# 51.net
KiCad netlist of a schematic drawn in Altium Designer
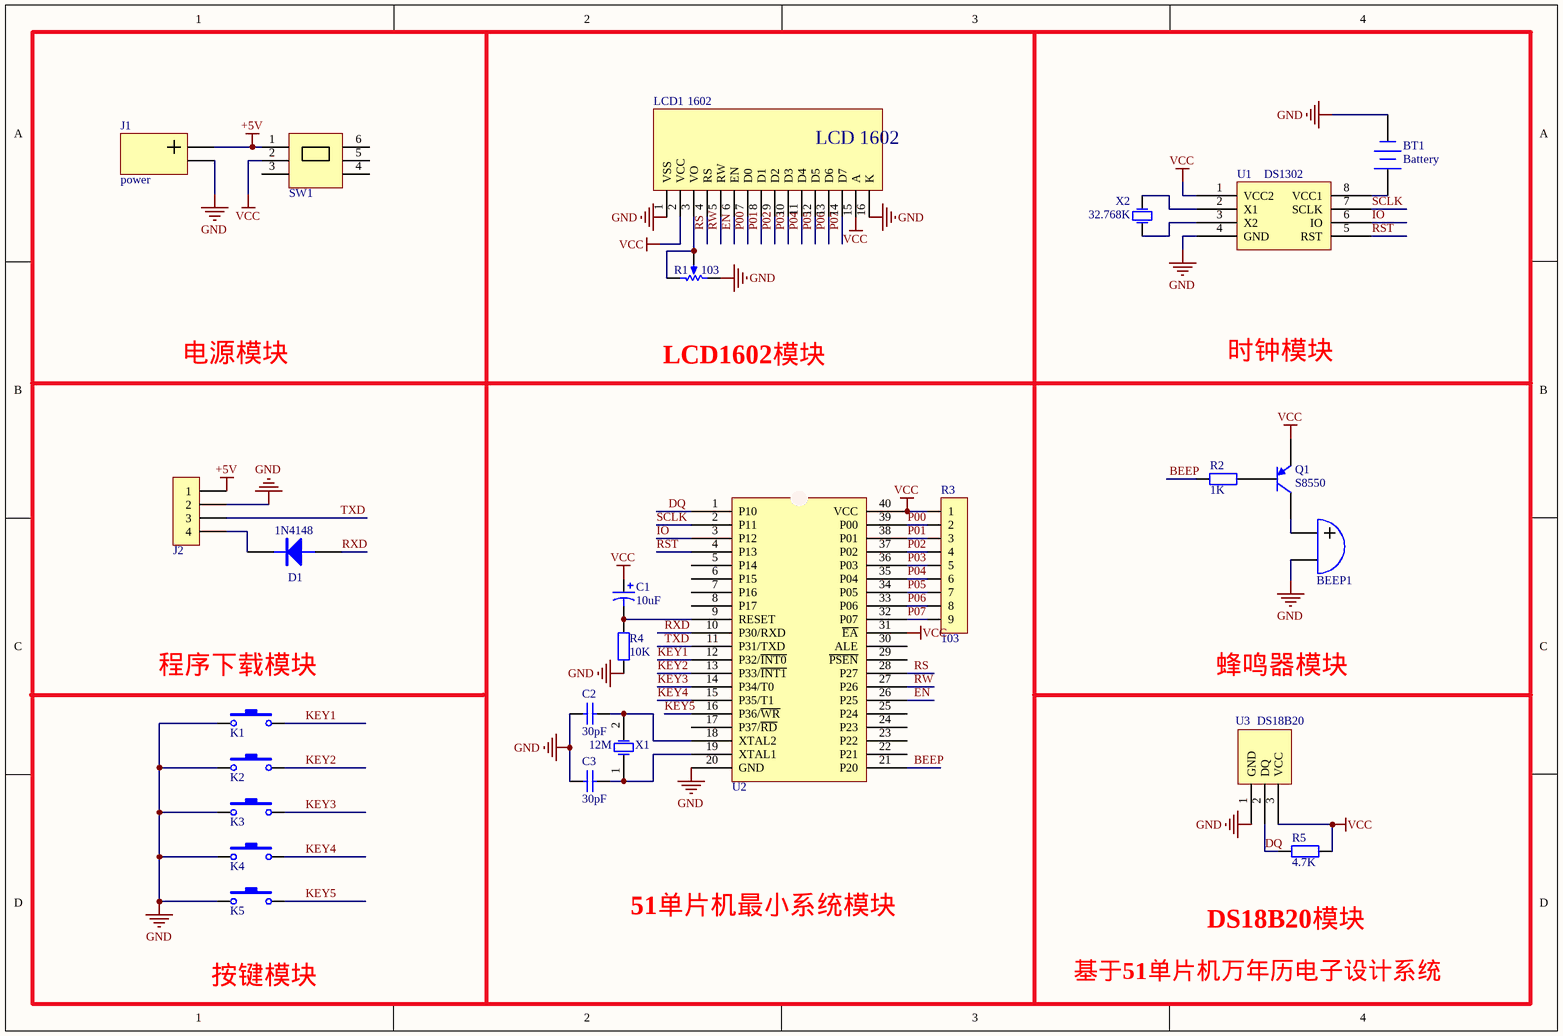
[diagram p0: 基于51单片机万年历电子设计系统.SchDoc]

(export (version "E")
  (design (tool "Eeschema 10.0.6"))
  (components
    (comp (ref "BEEP1") (value "BEEP") (footprint "BEEP") (libsource (lib "原理图库") (part "BEEP")))
    (comp (ref "BT1") (value "Battery") (footprint "CR-2032") (libsource (lib "MANUAL") (part "Battery")))
    (comp (ref "C1") (value "10uF") (footprint "CAP_2") (libsource (lib "原理图库") (part "CAP_2")))
    (comp (ref "C2") (value "30pF") (footprint "CAP") (libsource (lib "原理图库") (part "CAP")))
    (comp (ref "C3") (value "30pF") (footprint "CAP") (libsource (lib "原理图库") (part "CAP")))
    (comp (ref "D1") (value "1N4148") (footprint "1N4148") (libsource (lib "原理图库") (part "1N4148")))
    (comp (ref "J1") (value "power") (footprint "DC3.5") (libsource (lib "原理图库") (part "DC5.5")))
    (comp (ref "J2") (value "SENSOR") (footprint "SIP4") (libsource (lib "基于单片机温湿度报警器（带风扇）") (part "CON4")))
    (comp (ref "K1") (value "KEY") (footprint "SW2") (libsource (lib "原理图库") (part "KEY")))
    (comp (ref "K2") (value "KEY") (footprint "SW2") (libsource (lib "原理图库") (part "KEY")))
    (comp (ref "K3") (value "KEY") (footprint "SW2") (libsource (lib "原理图库") (part "KEY")))
    (comp (ref "K4") (value "KEY") (footprint "SW2") (libsource (lib "原理图库") (part "KEY")))
    (comp (ref "K5") (value "KEY") (footprint "SW2") (libsource (lib "原理图库") (part "KEY")))
    (comp (ref "LCD1") (value "1602") (footprint "1602") (libsource (lib "原理图库") (part "1602")))
    (comp (ref "Q1") (value "S8550") (footprint "PNP") (libsource (lib "原理图库") (part "PNP")))
    (comp (ref "R1") (value "103") (footprint "RES-B") (libsource (lib "原理图库") (part "RES-B")))
    (comp (ref "R2") (value "1K") (footprint "RES") (libsource (lib "") (part "Res_1")))
    (comp (ref "R3") (value "103") (footprint "SIP9") (libsource (lib "原理图库") (part "Header9")))
    (comp (ref "R4") (value "10K") (footprint "RES") (libsource (lib "原理图库") (part "Res")))
    (comp (ref "R5") (value "4.7K") (footprint "RES") (libsource (lib "") (part "Res_1")))
    (comp (ref "SW1") (value "SWT") (footprint "SWT") (libsource (lib "原理图库") (part "SWT")))
    (comp (ref "U1") (value "DS1302") (footprint "DIP8") (libsource (lib "MANUAL") (part "DS1302")))
    (comp (ref "U2") (value "STC89C52") (footprint "DIP40") (libsource (lib "原理图库") (part "STC89C52")))
    (comp (ref "U3") (value "DS18B20") (footprint "DS18B20") (libsource (lib "原理图库") (part "DS18B20")))
    (comp (ref "X1") (value "12M") (footprint "JZ") (libsource (lib "原理图库") (part "XTAL")))
    (comp (ref "X2") (value "32.768K") (footprint "XTAL2") (libsource (lib "Factory") (part "XTAL")))
  )
  (nets
    (net (code "1") (name "+5V") (class "Default")
      (node (ref "J1") (pin "1") (pinfunction "1_1") (pintype "passive"))
      (node (ref "J2") (pin "1") (pinfunction "1_1") (pintype "passive"))
      (node (ref "SW1") (pin "1") (pinfunction "0_1") (pintype "passive"))
    )
    (net (code "2") (name "/BEEP") (class "Default")
      (node (ref "R2") (pin "2") (pinfunction "2_2") (pintype "passive"))
      (node (ref "U2") (pin "21") (pinfunction "P20_21") (pintype "passive"))
    )
    (net (code "3") (name "/DQ") (class "Default")
      (node (ref "R5") (pin "2") (pinfunction "2_2") (pintype "passive"))
      (node (ref "U2") (pin "1") (pinfunction "P10_1") (pintype "passive"))
      (node (ref "U3") (pin "2") (pinfunction "DQ_2") (pintype "passive"))
    )
    (net (code "4") (name "/EN") (class "Default")
      (node (ref "LCD1") (pin "6") (pinfunction "EN_6") (pintype "passive"))
      (node (ref "U2") (pin "26") (pinfunction "P25_26") (pintype "passive"))
    )
    (net (code "5") (name "/IO") (class "Default")
      (node (ref "U1") (pin "6") (pinfunction "IO_6") (pintype "passive"))
      (node (ref "U2") (pin "3") (pinfunction "P12_3") (pintype "passive"))
    )
    (net (code "6") (name "/KEY1") (class "Default")
      (node (ref "K1") (pin "2") (pinfunction "2_2") (pintype "passive"))
      (node (ref "U2") (pin "12") (pinfunction "P32/~{INT0}_12") (pintype "passive"))
    )
    (net (code "7") (name "/KEY2") (class "Default")
      (node (ref "K2") (pin "2") (pinfunction "2_2") (pintype "passive"))
      (node (ref "U2") (pin "13") (pinfunction "P33/~{INT1}_13") (pintype "passive"))
    )
    (net (code "8") (name "/KEY3") (class "Default")
      (node (ref "K3") (pin "2") (pinfunction "2_2") (pintype "passive"))
      (node (ref "U2") (pin "14") (pinfunction "P34/T0_14") (pintype "passive"))
    )
    (net (code "9") (name "/KEY4") (class "Default")
      (node (ref "K4") (pin "2") (pinfunction "2_2") (pintype "passive"))
      (node (ref "U2") (pin "15") (pinfunction "P35/T1_15") (pintype "passive"))
    )
    (net (code "10") (name "/KEY5") (class "Default")
      (node (ref "K5") (pin "2") (pinfunction "2_2") (pintype "passive"))
      (node (ref "U2") (pin "16") (pinfunction "P36/~{WR}_16") (pintype "passive"))
    )
    (net (code "11") (name "/P00") (class "Default")
      (node (ref "LCD1") (pin "7") (pinfunction "D0_7") (pintype "passive"))
      (node (ref "R3") (pin "2") (pinfunction "2_2") (pintype "passive"))
      (node (ref "U2") (pin "39") (pinfunction "P00_39") (pintype "passive"))
    )
    (net (code "12") (name "/P01") (class "Default")
      (node (ref "LCD1") (pin "8") (pinfunction "D1_8") (pintype "passive"))
      (node (ref "R3") (pin "3") (pinfunction "3_3") (pintype "passive"))
      (node (ref "U2") (pin "38") (pinfunction "P01_38") (pintype "passive"))
    )
    (net (code "13") (name "/P02") (class "Default")
      (node (ref "LCD1") (pin "9") (pinfunction "D2_9") (pintype "passive"))
      (node (ref "R3") (pin "4") (pinfunction "4_4") (pintype "passive"))
      (node (ref "U2") (pin "37") (pinfunction "P02_37") (pintype "passive"))
    )
    (net (code "14") (name "/P03") (class "Default")
      (node (ref "LCD1") (pin "10") (pinfunction "D3_10") (pintype "passive"))
      (node (ref "R3") (pin "5") (pinfunction "5_5") (pintype "passive"))
      (node (ref "U2") (pin "36") (pinfunction "P03_36") (pintype "passive"))
    )
    (net (code "15") (name "/P04") (class "Default")
      (node (ref "LCD1") (pin "11") (pinfunction "D4_11") (pintype "passive"))
      (node (ref "R3") (pin "6") (pinfunction "6_6") (pintype "passive"))
      (node (ref "U2") (pin "35") (pinfunction "P04_35") (pintype "passive"))
    )
    (net (code "16") (name "/P05") (class "Default")
      (node (ref "LCD1") (pin "12") (pinfunction "D5_12") (pintype "passive"))
      (node (ref "R3") (pin "7") (pinfunction "7_7") (pintype "passive"))
      (node (ref "U2") (pin "34") (pinfunction "P05_34") (pintype "passive"))
    )
    (net (code "17") (name "/P06") (class "Default")
      (node (ref "LCD1") (pin "13") (pinfunction "D6_13") (pintype "passive"))
      (node (ref "R3") (pin "8") (pinfunction "8_8") (pintype "passive"))
      (node (ref "U2") (pin "33") (pinfunction "P06_33") (pintype "passive"))
    )
    (net (code "18") (name "/P07") (class "Default")
      (node (ref "LCD1") (pin "14") (pinfunction "D7_14") (pintype "passive"))
      (node (ref "R3") (pin "9") (pinfunction "9_9") (pintype "passive"))
      (node (ref "U2") (pin "32") (pinfunction "P07_32") (pintype "passive"))
    )
    (net (code "19") (name "/RS") (class "Default")
      (node (ref "LCD1") (pin "4") (pinfunction "RS_4") (pintype "passive"))
      (node (ref "U2") (pin "28") (pinfunction "P27_28") (pintype "passive"))
    )
    (net (code "20") (name "/RST") (class "Default")
      (node (ref "U1") (pin "5") (pinfunction "RST_5") (pintype "passive"))
      (node (ref "U2") (pin "4") (pinfunction "P13_4") (pintype "passive"))
    )
    (net (code "21") (name "/RW") (class "Default")
      (node (ref "LCD1") (pin "5") (pinfunction "RW_5") (pintype "passive"))
      (node (ref "U2") (pin "27") (pinfunction "P26_27") (pintype "passive"))
    )
    (net (code "22") (name "/RXD") (class "Default")
      (node (ref "D1") (pin "1") (pinfunction "A_1") (pintype "passive"))
      (node (ref "U2") (pin "10") (pinfunction "P30/RXD_10") (pintype "passive"))
    )
    (net (code "23") (name "/SCLK") (class "Default")
      (node (ref "U1") (pin "7") (pinfunction "SCLK_7") (pintype "passive"))
      (node (ref "U2") (pin "2") (pinfunction "P11_2") (pintype "passive"))
    )
    (net (code "24") (name "/TXD") (class "Default")
      (node (ref "J2") (pin "3") (pinfunction "3_3") (pintype "passive"))
      (node (ref "U2") (pin "11") (pinfunction "P31/TXD_11") (pintype "passive"))
    )
    (net (code "25") (name "GND") (class "Default")
      (node (ref "BEEP1") (pin "2") (pinfunction "2_2") (pintype "passive"))
      (node (ref "BT1") (pin "2") (pinfunction "-_2") (pintype "passive"))
      (node (ref "C2") (pin "1") (pinfunction "1_1") (pintype "passive"))
      (node (ref "C3") (pin "1") (pinfunction "1_1") (pintype "passive"))
      (node (ref "J1") (pin "2") (pinfunction "2_2") (pintype "passive"))
      (node (ref "J2") (pin "2") (pinfunction "2_2") (pintype "passive"))
      (node (ref "K1") (pin "1") (pinfunction "1_1") (pintype "passive"))
      (node (ref "K2") (pin "1") (pinfunction "1_1") (pintype "passive"))
      (node (ref "K3") (pin "1") (pinfunction "1_1") (pintype "passive"))
      (node (ref "K4") (pin "1") (pinfunction "1_1") (pintype "passive"))
      (node (ref "K5") (pin "1") (pinfunction "1_1") (pintype "passive"))
      (node (ref "LCD1") (pin "1") (pinfunction "VSS_1") (pintype "passive"))
      (node (ref "LCD1") (pin "16") (pinfunction "K_16") (pintype "passive"))
      (node (ref "R1") (pin "1") (pinfunction "1_1") (pintype "passive"))
      (node (ref "R4") (pin "1") (pinfunction "1_1") (pintype "passive"))
      (node (ref "U1") (pin "4") (pinfunction "GND_4") (pintype "passive"))
      (node (ref "U2") (pin "20") (pinfunction "GND_20") (pintype "passive"))
      (node (ref "U3") (pin "1") (pinfunction "GND_1") (pintype "passive"))
    )
    (net (code "26") (name "Net-(BEEP1-Pad1)") (class "Default")
      (node (ref "BEEP1") (pin "1") (pinfunction "1_1") (pintype "passive"))
      (node (ref "Q1") (pin "C") (pinfunction "C_C") (pintype "passive"))
    )
    (net (code "27") (name "Net-(BT1-+)") (class "Default")
      (node (ref "BT1") (pin "1") (pinfunction "+_1") (pintype "passive"))
      (node (ref "U1") (pin "8") (pinfunction "VCC1_8") (pintype "passive"))
    )
    (net (code "28") (name "Net-(D1-K)") (class "Default")
      (node (ref "D1") (pin "2") (pinfunction "K_2") (pintype "passive"))
      (node (ref "J2") (pin "4") (pinfunction "4_4") (pintype "passive"))
    )
    (net (code "29") (name "Net-(LCD1-VO)") (class "Default")
      (node (ref "LCD1") (pin "3") (pinfunction "VO_3") (pintype "passive"))
      (node (ref "R1") (pin "2") (pinfunction "2_2") (pintype "passive"))
      (node (ref "R1") (pin "3") (pinfunction "3_3") (pintype "passive"))
    )
    (net (code "30") (name "Net-(Q1-PadB)") (class "Default")
      (node (ref "Q1") (pin "B") (pinfunction "B_B") (pintype "passive"))
      (node (ref "R2") (pin "1") (pinfunction "1_1") (pintype "passive"))
    )
    (net (code "31") (name "Net-(U1-X1)") (class "Default")
      (node (ref "U1") (pin "2") (pinfunction "X1_2") (pintype "passive"))
      (node (ref "X2") (pin "2") (pinfunction "OSC2_2") (pintype "passive"))
    )
    (net (code "32") (name "Net-(U1-X2)") (class "Default")
      (node (ref "U1") (pin "3") (pinfunction "X2_3") (pintype "passive"))
      (node (ref "X2") (pin "1") (pinfunction "OSC1_1") (pintype "passive"))
    )
    (net (code "33") (name "Net-(U2-RESET)") (class "Default")
      (node (ref "C1") (pin "2") (pinfunction "2_2") (pintype "passive"))
      (node (ref "R4") (pin "2") (pinfunction "2_2") (pintype "passive"))
      (node (ref "U2") (pin "9") (pinfunction "RESET_9") (pintype "passive"))
    )
    (net (code "34") (name "Net-(U2-XTAL1)") (class "Default")
      (node (ref "C3") (pin "2") (pinfunction "2_2") (pintype "passive"))
      (node (ref "U2") (pin "19") (pinfunction "XTAL1_19") (pintype "passive"))
      (node (ref "X1") (pin "1") (pinfunction "OSC1_1") (pintype "passive"))
    )
    (net (code "35") (name "Net-(U2-XTAL2)") (class "Default")
      (node (ref "C2") (pin "2") (pinfunction "2_2") (pintype "passive"))
      (node (ref "U2") (pin "18") (pinfunction "XTAL2_18") (pintype "passive"))
      (node (ref "X1") (pin "2") (pinfunction "OSC2_2") (pintype "passive"))
    )
    (net (code "36") (name "VCC") (class "Default")
      (node (ref "C1") (pin "1") (pinfunction "1_1") (pintype "passive"))
      (node (ref "LCD1") (pin "15") (pinfunction "A_15") (pintype "passive"))
      (node (ref "LCD1") (pin "2") (pinfunction "VCC_2") (pintype "passive"))
      (node (ref "Q1") (pin "E") (pinfunction "E_E") (pintype "passive"))
      (node (ref "R3") (pin "1") (pinfunction "1_1") (pintype "passive"))
      (node (ref "R5") (pin "1") (pinfunction "1_1") (pintype "passive"))
      (node (ref "SW1") (pin "2") (pinfunction "1_2") (pintype "passive"))
      (node (ref "U1") (pin "1") (pinfunction "VCC2_1") (pintype "passive"))
      (node (ref "U2") (pin "31") (pinfunction "~{EA}_31") (pintype "passive"))
      (node (ref "U2") (pin "40") (pinfunction "VCC_40") (pintype "passive"))
      (node (ref "U3") (pin "3") (pinfunction "VCC_3") (pintype "passive"))
    )
    (net (code "37") (name "unconnected-(SW1-2-Pad3)") (class "Default")
      (node (ref "SW1") (pin "3") (pinfunction "2_3") (pintype "passive"))
    )
    (net (code "38") (name "unconnected-(SW1-3-Pad4)") (class "Default")
      (node (ref "SW1") (pin "4") (pinfunction "3_4") (pintype "passive"))
    )
    (net (code "39") (name "unconnected-(SW1-4-Pad5)") (class "Default")
      (node (ref "SW1") (pin "5") (pinfunction "4_5") (pintype "passive"))
    )
    (net (code "40") (name "unconnected-(SW1-5-Pad6)") (class "Default")
      (node (ref "SW1") (pin "6") (pinfunction "5_6") (pintype "passive"))
    )
    (net (code "41") (name "unconnected-(U2-ALE-Pad30)") (class "Default")
      (node (ref "U2") (pin "30") (pinfunction "ALE_30") (pintype "passive"))
    )
    (net (code "42") (name "unconnected-(U2-P14-Pad5)") (class "Default")
      (node (ref "U2") (pin "5") (pinfunction "P14_5") (pintype "passive"))
    )
    (net (code "43") (name "unconnected-(U2-P15-Pad6)") (class "Default")
      (node (ref "U2") (pin "6") (pinfunction "P15_6") (pintype "passive"))
    )
    (net (code "44") (name "unconnected-(U2-P16-Pad7)") (class "Default")
      (node (ref "U2") (pin "7") (pinfunction "P16_7") (pintype "passive"))
    )
    (net (code "45") (name "unconnected-(U2-P17-Pad8)") (class "Default")
      (node (ref "U2") (pin "8") (pinfunction "P17_8") (pintype "passive"))
    )
    (net (code "46") (name "unconnected-(U2-P21-Pad22)") (class "Default")
      (node (ref "U2") (pin "22") (pinfunction "P21_22") (pintype "passive"))
    )
    (net (code "47") (name "unconnected-(U2-P22-Pad23)") (class "Default")
      (node (ref "U2") (pin "23") (pinfunction "P22_23") (pintype "passive"))
    )
    (net (code "48") (name "unconnected-(U2-P23-Pad24)") (class "Default")
      (node (ref "U2") (pin "24") (pinfunction "P23_24") (pintype "passive"))
    )
    (net (code "49") (name "unconnected-(U2-P24-Pad25)") (class "Default")
      (node (ref "U2") (pin "25") (pinfunction "P24_25") (pintype "passive"))
    )
    (net (code "50") (name "unconnected-(U2-P37{slash}~{RD}-Pad17)") (class "Default")
      (node (ref "U2") (pin "17") (pinfunction "P37/~{RD}_17") (pintype "passive"))
    )
    (net (code "51") (name "unconnected-(U2-~{PSEN}-Pad29)") (class "Default")
      (node (ref "U2") (pin "29") (pinfunction "~{PSEN}_29") (pintype "passive"))
    )
  )
)
